# Line.net
KiCad netlist of a schematic drawn in Altium Designer
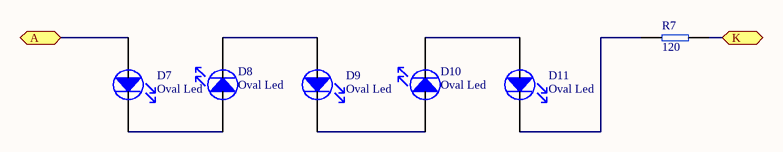
[diagram p0: Line.SchDoc]

(export (version "E")
  (design (tool "Eeschema 10.0.6"))
  (components
    (comp (ref "D7")
      (value "Oval Led")
      (footprint "LED")
      (description "LED estándar - Montaje interfacial Red Oval LED")
      (fields (field (name "MPN") "C566C-RFN-CV0W0BB2"))
      (libsource (lib "Miscellaneous Devices") (part "Oval Led"))
    )
    (comp (ref "D8")
      (value "Oval Led")
      (footprint "LED")
      (description "LED estándar - Montaje interfacial Red Oval LED")
      (fields (field (name "MPN") "C566C-RFN-CV0W0BB2"))
      (libsource (lib "Miscellaneous Devices") (part "Oval Led"))
    )
    (comp (ref "D9")
      (value "Oval Led")
      (footprint "LED")
      (description "LED estándar - Montaje interfacial Red Oval LED")
      (fields (field (name "MPN") "C566C-RFN-CV0W0BB2"))
      (libsource (lib "Miscellaneous Devices") (part "Oval Led"))
    )
    (comp (ref "D10")
      (value "Oval Led")
      (footprint "LED")
      (description "LED estándar - Montaje interfacial Red Oval LED")
      (fields (field (name "MPN") "C566C-RFN-CV0W0BB2"))
      (libsource (lib "Miscellaneous Devices") (part "Oval Led"))
    )
    (comp (ref "D11")
      (value "Oval Led")
      (footprint "LED")
      (description "LED estándar - Montaje interfacial Red Oval LED")
      (fields (field (name "MPN") "C566C-RFN-CV0W0BB2"))
      (libsource (lib "Miscellaneous Devices") (part "Oval Led"))
    )
    (comp (ref "R7")
      (value "120")
      (footprint "RES2512")
      (description "Resistores de película gruesa - SMD 1watt 120ohms 5%")
      (fields (field (name "MPN") "CRCW2512120RJNEG") (field (name "Comment") "RES120"))
      (libsource (lib "Miscellaneous Devices") (part "RES120"))
    )
  )
  (nets
    (net (code "1") (name "/A") (class "Default")
      (node (ref "D7") (pin "A") (pinfunction "Anode_A") (pintype "passive"))
    )
    (net (code "2") (name "/K") (class "Default")
      (node (ref "R7") (pin "2") (pinfunction "neg_2") (pintype "passive"))
    )
    (net (code "3") (name "Net-(D7-Cathode)") (class "Default")
      (node (ref "D7") (pin "K") (pinfunction "Cathode_K") (pintype "passive"))
      (node (ref "D8") (pin "A") (pinfunction "Anode_A") (pintype "passive"))
    )
    (net (code "4") (name "Net-(D8-Cathode)") (class "Default")
      (node (ref "D8") (pin "K") (pinfunction "Cathode_K") (pintype "passive"))
      (node (ref "D9") (pin "A") (pinfunction "Anode_A") (pintype "passive"))
    )
    (net (code "5") (name "Net-(D10-Anode)") (class "Default")
      (node (ref "D10") (pin "A") (pinfunction "Anode_A") (pintype "passive"))
      (node (ref "D9") (pin "K") (pinfunction "Cathode_K") (pintype "passive"))
    )
    (net (code "6") (name "Net-(D10-Cathode)") (class "Default")
      (node (ref "D10") (pin "K") (pinfunction "Cathode_K") (pintype "passive"))
      (node (ref "D11") (pin "A") (pinfunction "Anode_A") (pintype "passive"))
    )
    (net (code "7") (name "Net-(D11-Cathode)") (class "Default")
      (node (ref "D11") (pin "K") (pinfunction "Cathode_K") (pintype "passive"))
      (node (ref "R7") (pin "1") (pinfunction "pos_1") (pintype "passive"))
    )
  )
)
